# USB_Programmer.net
KiCad netlist of a schematic drawn in Altium Designer
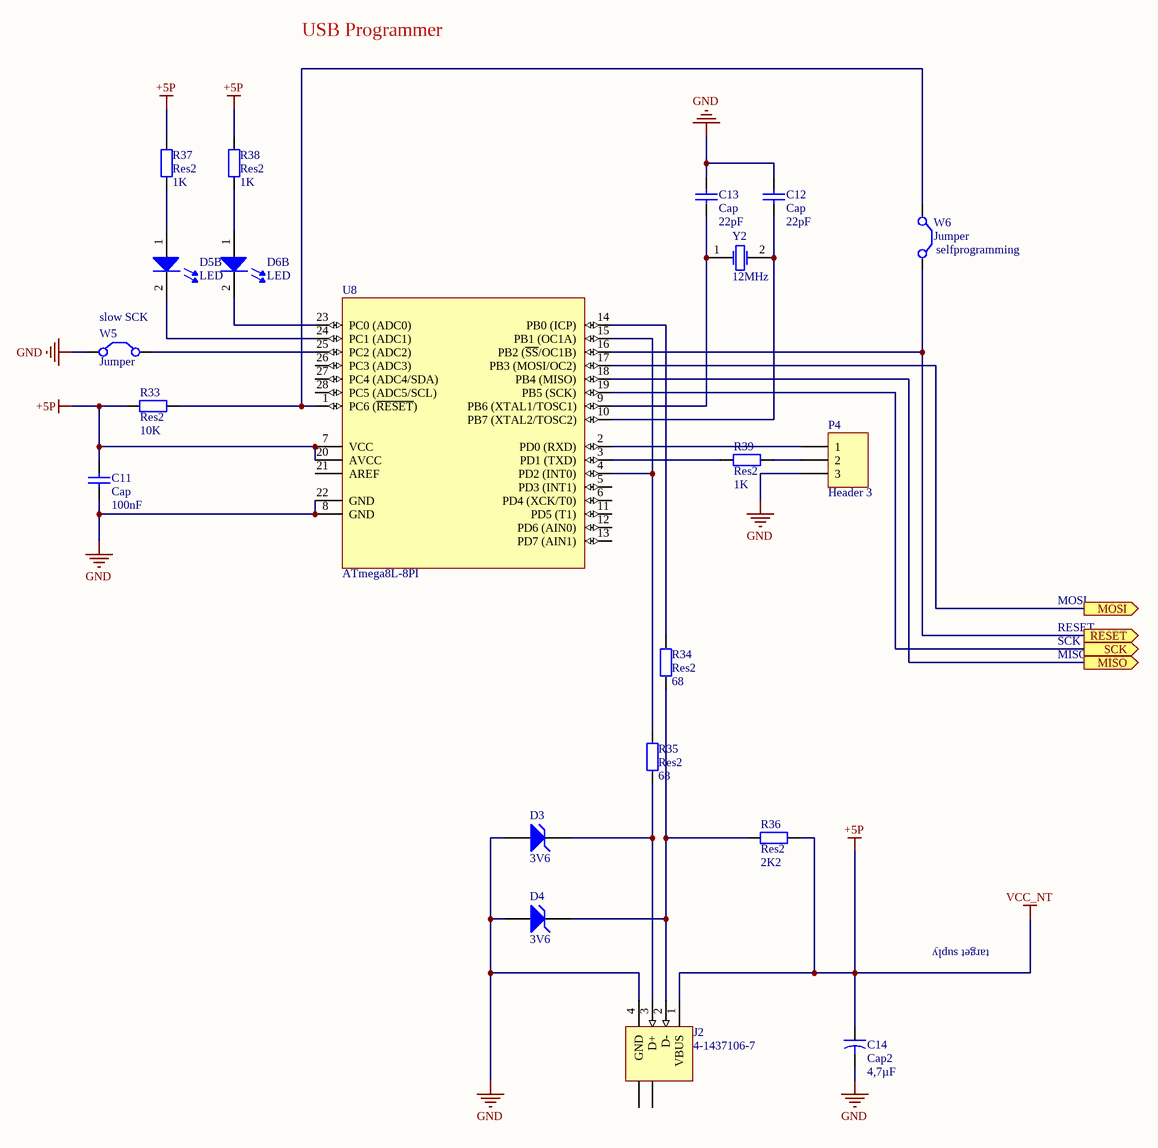
[diagram p0: USB_Programmer.SchDoc]

(export (version "E")
  (design (tool "Eeschema 10.0.6"))
  (components
    (comp (ref "C11")
      (value "Cap")
      (footprint "Miscellaneous Devices:RAD-0.1")
      (description "Capacitor")
      (fields (field (name "ALTIUM_VALUE") "100nF") (field (name "PUBLISHER") "Altium Limited"))
      (libsource (lib "Miscellaneous Devices") (part "Cap"))
    )
    (comp (ref "C12")
      (value "Cap")
      (footprint "Miscellaneous Devices:RAD-0.1")
      (description "Capacitor")
      (fields (field (name "ALTIUM_VALUE") "22pF") (field (name "PUBLISHER") "Altium Limited"))
      (libsource (lib "Miscellaneous Devices") (part "Cap"))
    )
    (comp (ref "C13")
      (value "Cap")
      (footprint "Miscellaneous Devices:RAD-0.1")
      (description "Capacitor")
      (fields (field (name "ALTIUM_VALUE") "22pF") (field (name "PUBLISHER") "Altium Limited"))
      (libsource (lib "Miscellaneous Devices") (part "Cap"))
    )
    (comp (ref "C14")
      (value "Cap2")
      (footprint "CAPR5-4X5")
      (description "Capacitor")
      (fields (field (name "ALTIUM_VALUE") "4,7µF") (field (name "PUBLISHER") "Altium Limited"))
      (libsource (lib "Miscellaneous Devices") (part "Cap2"))
    )
    (comp (ref "D3")
      (value "3V6")
      (footprint "DO-7")
      (description "Zener Diode")
      (fields (field (name "PUBLISHER") "Altium Limited"))
      (libsource (lib "Miscellaneous Devices") (part "D Zener"))
    )
    (comp (ref "D4")
      (value "3V6")
      (footprint "DO-7")
      (description "Zener Diode")
      (fields (field (name "PUBLISHER") "Altium Limited"))
      (libsource (lib "Miscellaneous Devices") (part "D Zener"))
    )
    (comp (ref "D5")
      (value "LED")
      (footprint "LED 3mm")
      (description "LED bedrahtet")
      (libsource (lib "StdBT") (part "LED Std"))
    )
    (comp (ref "D6")
      (value "LED")
      (footprint "LED 3mm")
      (description "LED bedrahtet")
      (libsource (lib "StdBT") (part "LED Std"))
    )
    (comp (ref "J2")
      (value "4-1437106-7")
      (footprint "1437106")
      (description "USB 1.1, Right Angle, Thru-Hole, B Type, Receptacle, 4 Position, White")
      (fields (field (name "PUBLISHER") "Altium Limited"))
      (libsource (lib "AMP Serial Bus USB") (part "4-1437106-7"))
    )
    (comp (ref "P4")
      (value "Header 3")
      (footprint "HDR1X3")
      (description "Header, 3-Pin")
      (fields (field (name "PUBLISHER") "Altium Limited"))
      (libsource (lib "Miscellaneous Connectors") (part "Header 3"))
    )
    (comp (ref "R33")
      (value "Res2")
      (footprint "AXIAL-0.4")
      (description "Resistor")
      (fields (field (name "ALTIUM_VALUE") "10K") (field (name "PUBLISHER") "Altium Limited"))
      (libsource (lib "Miscellaneous Devices") (part "Res2"))
    )
    (comp (ref "R34")
      (value "Res2")
      (footprint "AXIAL-0.4")
      (description "Resistor")
      (fields (field (name "ALTIUM_VALUE") "68") (field (name "PUBLISHER") "Altium Limited"))
      (libsource (lib "") (part "Res2_1"))
    )
    (comp (ref "R35")
      (value "Res2")
      (footprint "AXIAL-0.4")
      (description "Resistor")
      (fields (field (name "ALTIUM_VALUE") "68") (field (name "PUBLISHER") "Altium Limited"))
      (libsource (lib "") (part "Res2_1"))
    )
    (comp (ref "R36")
      (value "Res2")
      (footprint "AXIAL-0.4")
      (description "Resistor")
      (fields (field (name "ALTIUM_VALUE") "2K2") (field (name "PUBLISHER") "Altium Limited"))
      (libsource (lib "Miscellaneous Devices") (part "Res2"))
    )
    (comp (ref "R37")
      (value "Res2")
      (footprint "AXIAL-0.4")
      (description "Resistor")
      (fields (field (name "ALTIUM_VALUE") "1K") (field (name "PUBLISHER") "Altium Limited"))
      (libsource (lib "") (part "Res2_2"))
    )
    (comp (ref "R38")
      (value "Res2")
      (footprint "AXIAL-0.4")
      (description "Resistor")
      (fields (field (name "ALTIUM_VALUE") "1K") (field (name "PUBLISHER") "Altium Limited"))
      (libsource (lib "") (part "Res2_2"))
    )
    (comp (ref "R39")
      (value "Res2")
      (footprint "AXIAL-0.4")
      (description "Resistor")
      (fields (field (name "ALTIUM_VALUE") "1K") (field (name "PUBLISHER") "Altium Limited"))
      (libsource (lib "Miscellaneous Devices") (part "Res2"))
    )
    (comp (ref "U8")
      (value "ATmega8L-8PI")
      (footprint "28P3")
      (description "8-Bit AVR Microcontroller with 8K Bytes of In-System Programmable Flash Memory")
      (fields (field (name "PUBLISHER") "Altium Limited"))
      (libsource (lib "Atmel Microcontroller 8-Bit AVR") (part "ATmega8L-8PI"))
    )
    (comp (ref "W5")
      (value "Jumper")
      (footprint "Miscellaneous Connectors:HDR1X2")
      (description "Jumper Wire")
      (fields (field (name "PUBLISHER") "Altium Limited"))
      (libsource (lib "Miscellaneous Devices") (part "Jumper"))
    )
    (comp (ref "W6")
      (value "Jumper")
      (footprint "Miscellaneous Connectors:HDR1X2")
      (description "Jumper Wire")
      (fields (field (name "PUBLISHER") "Altium Limited"))
      (libsource (lib "Miscellaneous Devices") (part "Jumper"))
    )
    (comp (ref "Y2")
      (value "12MHz")
      (footprint "Quarz HC49-4HL")
      (libsource (lib "StdBT") (part "Quarz HC49-4HL"))
    )
  )
  (nets
    (net (code "1") (name "+5P") (class "Default")
      (node (ref "C11") (pin "2") (pinfunction "2_2") (pintype "passive"))
      (node (ref "C14") (pin "1") (pinfunction "1_1") (pintype "passive"))
      (node (ref "J2") (pin "1") (pinfunction "VBUS_1") (pintype "power_in"))
      (node (ref "R33") (pin "1") (pinfunction "1_1") (pintype "passive"))
      (node (ref "R36") (pin "2") (pinfunction "2_2") (pintype "passive"))
      (node (ref "R37") (pin "2") (pinfunction "2_2") (pintype "passive"))
      (node (ref "R38") (pin "2") (pinfunction "2_2") (pintype "passive"))
      (node (ref "U8") (pin "20") (pinfunction "AVCC_20") (pintype "power_in"))
      (node (ref "U8") (pin "7") (pinfunction "VCC_7") (pintype "power_in"))
    )
    (net (code "2") (name "/MISO") (class "Default")
      (node (ref "U8") (pin "18") (pinfunction "PB4_(MISO)_18") (pintype "bidirectional"))
    )
    (net (code "3") (name "/MOSI") (class "Default")
      (node (ref "U8") (pin "17") (pinfunction "PB3_(MOSI/OC2)_17") (pintype "bidirectional"))
    )
    (net (code "4") (name "/RESET") (class "Default")
      (node (ref "U8") (pin "16") (pinfunction "PB2_(~{SS}/OC1B)_16") (pintype "bidirectional"))
      (node (ref "W6") (pin "2") (pinfunction "C2_2") (pintype "passive"))
    )
    (net (code "5") (name "/SCK") (class "Default")
      (node (ref "U8") (pin "19") (pinfunction "PB5_(SCK)_19") (pintype "bidirectional"))
    )
    (net (code "6") (name "GND") (class "Default")
      (node (ref "C11") (pin "1") (pinfunction "1_1") (pintype "passive"))
      (node (ref "C12") (pin "1") (pinfunction "1_1") (pintype "passive"))
      (node (ref "C13") (pin "1") (pinfunction "1_1") (pintype "passive"))
      (node (ref "C14") (pin "2") (pinfunction "2_2") (pintype "passive"))
      (node (ref "D3") (pin "1") (pinfunction "A_1") (pintype "passive"))
      (node (ref "D4") (pin "1") (pinfunction "A_1") (pintype "passive"))
      (node (ref "J2") (pin "4") (pinfunction "GND_4") (pintype "power_in"))
      (node (ref "P4") (pin "3") (pinfunction "3_3") (pintype "passive"))
      (node (ref "U8") (pin "22") (pinfunction "GND_22") (pintype "power_in"))
      (node (ref "U8") (pin "8") (pinfunction "GND_8") (pintype "power_in"))
      (node (ref "W5") (pin "1") (pinfunction "C1_1") (pintype "passive"))
    )
    (net (code "7") (name "Net-(D3-K)") (class "Default")
      (node (ref "D3") (pin "2") (pinfunction "K_2") (pintype "passive"))
      (node (ref "J2") (pin "3") (pinfunction "D+_3") (pintype "input"))
      (node (ref "R35") (pin "2") (pinfunction "2_2") (pintype "passive"))
    )
    (net (code "8") (name "Net-(D4-K)") (class "Default")
      (node (ref "D4") (pin "2") (pinfunction "K_2") (pintype "passive"))
      (node (ref "J2") (pin "2") (pinfunction "D-_2") (pintype "input"))
      (node (ref "R34") (pin "2") (pinfunction "2_2") (pintype "passive"))
      (node (ref "R36") (pin "1") (pinfunction "1_1") (pintype "passive"))
    )
    (net (code "9") (name "Net-(D5-Pad1)") (class "Default")
      (node (ref "D5") (pin "1") (pintype "passive"))
      (node (ref "R37") (pin "1") (pinfunction "1_1") (pintype "passive"))
    )
    (net (code "10") (name "Net-(D6-Pad1)") (class "Default")
      (node (ref "D6") (pin "1") (pintype "passive"))
      (node (ref "R38") (pin "1") (pinfunction "1_1") (pintype "passive"))
    )
    (net (code "11") (name "Net-(P4-Pad2)") (class "Default")
      (node (ref "P4") (pin "2") (pinfunction "2_2") (pintype "passive"))
      (node (ref "R39") (pin "2") (pinfunction "2_2") (pintype "passive"))
    )
    (net (code "12") (name "Net-(U8-PB0_(ICP))") (class "Default")
      (node (ref "R34") (pin "1") (pinfunction "1_1") (pintype "passive"))
      (node (ref "U8") (pin "14") (pinfunction "PB0_(ICP)_14") (pintype "bidirectional"))
    )
    (net (code "13") (name "Net-(U8-PB1_(OC1A))") (class "Default")
      (node (ref "R35") (pin "1") (pinfunction "1_1") (pintype "passive"))
      (node (ref "U8") (pin "15") (pinfunction "PB1_(OC1A)_15") (pintype "bidirectional"))
      (node (ref "U8") (pin "4") (pinfunction "PD2_(INT0)_4") (pintype "bidirectional"))
    )
    (net (code "14") (name "Net-(U8-PB6_(XTAL1{slash}TOSC1))") (class "Default")
      (node (ref "C13") (pin "2") (pinfunction "2_2") (pintype "passive"))
      (node (ref "U8") (pin "9") (pinfunction "PB6_(XTAL1/TOSC1)_9") (pintype "bidirectional"))
      (node (ref "Y2") (pin "1") (pinfunction "1_1") (pintype "passive"))
    )
    (net (code "15") (name "Net-(U8-PB7_(XTAL2{slash}TOSC2))") (class "Default")
      (node (ref "C12") (pin "2") (pinfunction "2_2") (pintype "passive"))
      (node (ref "U8") (pin "10") (pinfunction "PB7_(XTAL2/TOSC2)_10") (pintype "bidirectional"))
      (node (ref "Y2") (pin "2") (pinfunction "2_2") (pintype "passive"))
    )
    (net (code "16") (name "Net-(U8-PC0_(ADC0))") (class "Default")
      (node (ref "D6") (pin "2") (pintype "passive"))
      (node (ref "U8") (pin "23") (pinfunction "PC0_(ADC0)_23") (pintype "bidirectional"))
    )
    (net (code "17") (name "Net-(U8-PC1_(ADC1))") (class "Default")
      (node (ref "D5") (pin "2") (pintype "passive"))
      (node (ref "U8") (pin "24") (pinfunction "PC1_(ADC1)_24") (pintype "bidirectional"))
    )
    (net (code "18") (name "Net-(U8-PC2_(ADC2))") (class "Default")
      (node (ref "U8") (pin "25") (pinfunction "PC2_(ADC2)_25") (pintype "bidirectional"))
      (node (ref "W5") (pin "2") (pinfunction "C2_2") (pintype "passive"))
    )
    (net (code "19") (name "Net-(U8-PC6_(~{RESET}))") (class "Default")
      (node (ref "R33") (pin "2") (pinfunction "2_2") (pintype "passive"))
      (node (ref "U8") (pin "1") (pinfunction "PC6_(~{RESET})_1") (pintype "bidirectional"))
      (node (ref "W6") (pin "1") (pinfunction "C1_1") (pintype "passive"))
    )
    (net (code "20") (name "Net-(U8-PD0_(RXD))") (class "Default")
      (node (ref "P4") (pin "1") (pinfunction "1_1") (pintype "passive"))
      (node (ref "U8") (pin "2") (pinfunction "PD0_(RXD)_2") (pintype "bidirectional"))
    )
    (net (code "21") (name "Net-(U8-PD1_(TXD))") (class "Default")
      (node (ref "R39") (pin "1") (pinfunction "1_1") (pintype "passive"))
      (node (ref "U8") (pin "3") (pinfunction "PD1_(TXD)_3") (pintype "bidirectional"))
    )
    (net (code "22") (name "unconnected-(J2-SHLD-Pad5)") (class "Default")
      (node (ref "J2") (pin "5") (pinfunction "SHLD_5") (pintype "passive"))
    )
    (net (code "23") (name "unconnected-(J2-SHLD-Pad6)") (class "Default")
      (node (ref "J2") (pin "6") (pinfunction "SHLD_6") (pintype "passive"))
    )
    (net (code "24") (name "unconnected-(U8-AREF-Pad21)") (class "Default")
      (node (ref "U8") (pin "21") (pinfunction "AREF_21") (pintype "passive"))
    )
    (net (code "25") (name "unconnected-(U8-PC3_(ADC3)-Pad26)") (class "Default")
      (node (ref "U8") (pin "26") (pinfunction "PC3_(ADC3)_26") (pintype "bidirectional"))
    )
    (net (code "26") (name "unconnected-(U8-PC4_(ADC4{slash}SDA)-Pad27)") (class "Default")
      (node (ref "U8") (pin "27") (pinfunction "PC4_(ADC4/SDA)_27") (pintype "bidirectional"))
    )
    (net (code "27") (name "unconnected-(U8-PC5_(ADC5{slash}SCL)-Pad28)") (class "Default")
      (node (ref "U8") (pin "28") (pinfunction "PC5_(ADC5/SCL)_28") (pintype "bidirectional"))
    )
    (net (code "28") (name "unconnected-(U8-PD3_(INT1)-Pad5)") (class "Default")
      (node (ref "U8") (pin "5") (pinfunction "PD3_(INT1)_5") (pintype "bidirectional"))
    )
    (net (code "29") (name "unconnected-(U8-PD4_(XCK{slash}T0)-Pad6)") (class "Default")
      (node (ref "U8") (pin "6") (pinfunction "PD4_(XCK/T0)_6") (pintype "bidirectional"))
    )
    (net (code "30") (name "unconnected-(U8-PD5_(T1)-Pad11)") (class "Default")
      (node (ref "U8") (pin "11") (pinfunction "PD5_(T1)_11") (pintype "bidirectional"))
    )
    (net (code "31") (name "unconnected-(U8-PD6_(AIN0)-Pad12)") (class "Default")
      (node (ref "U8") (pin "12") (pinfunction "PD6_(AIN0)_12") (pintype "bidirectional"))
    )
    (net (code "32") (name "unconnected-(U8-PD7_(AIN1)-Pad13)") (class "Default")
      (node (ref "U8") (pin "13") (pinfunction "PD7_(AIN1)_13") (pintype "bidirectional"))
    )
  )
)
